# Top.net
KiCad netlist of a schematic drawn in Altium Designer
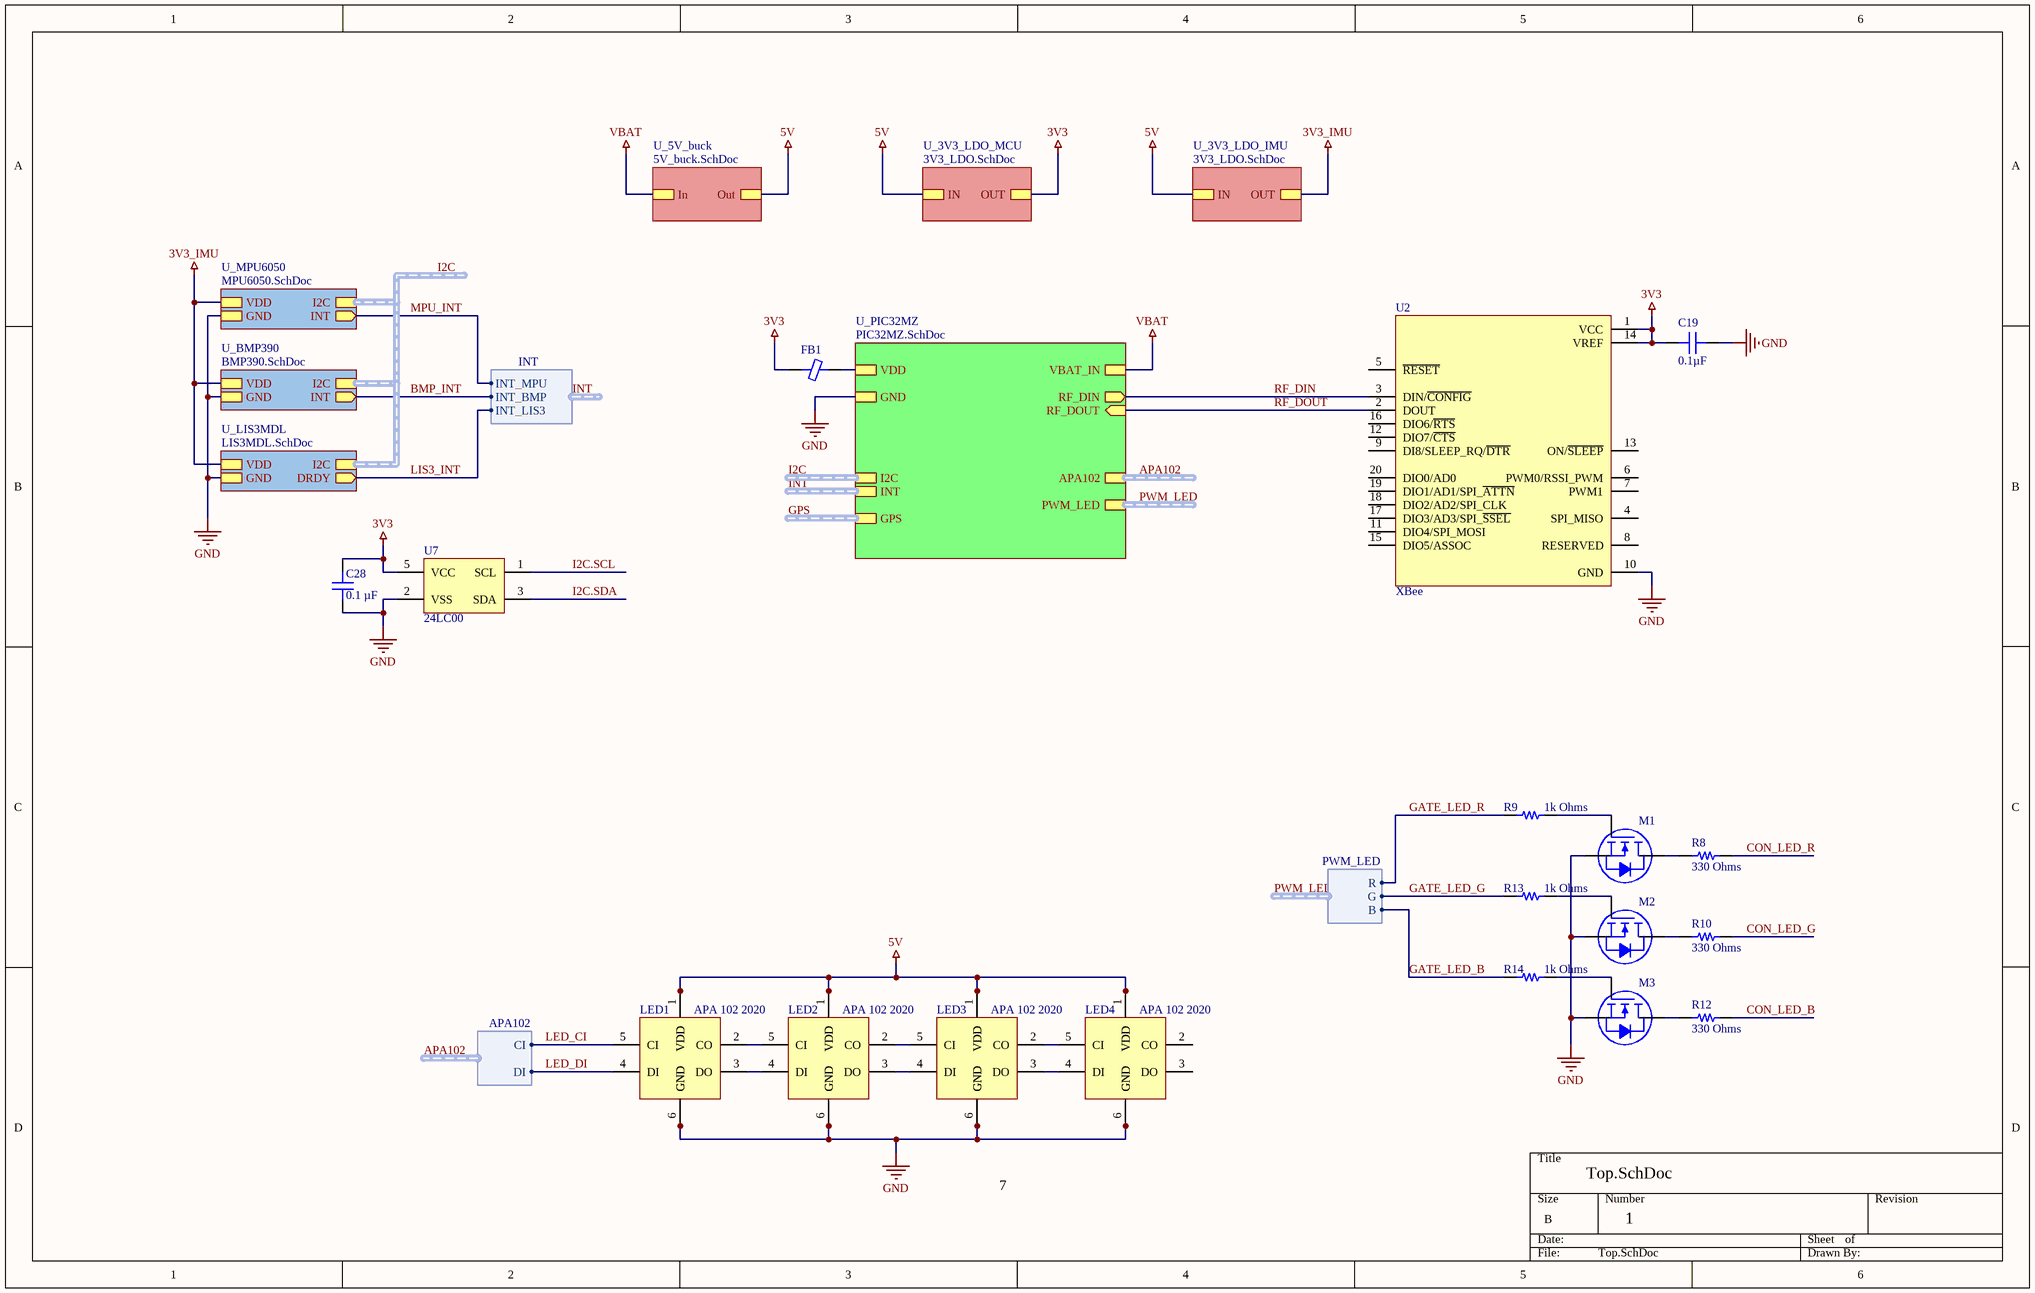
[diagram p0: Top.SchDoc]

(export (version "E")
  (design (tool "Eeschema 10.0.6"))
  (components
    (comp (ref "C19")
      (value "0.1µF")
      (footprint "CAP 0603_1608")
      (description "CAP CER 0.1UF 50V X7R 0603")
      (fields (field (name "PART NUMBER") "LD035C104JAB2A") (field (name "MANUFACTURER") "AVX Corporation"))
      (libsource (lib "Celestial Altium Library - altium_library") (part "Capacitor"))
    )
    (comp (ref "C28")
      (value "0.1 µF")
      (footprint "CAP 0402_1005")
      (description "CAP CER 0.1UF 16V X7R 0402")
      (fields (field (name "PART NUMBER") "C0402C104K4RACAUTO") (field (name "MANUFACTURER") "KEMET"))
      (libsource (lib "Celestial Altium Library - altium_library") (part "Capacitor"))
    )
    (comp (ref "FB1")
      (value "~")
      (footprint "FER 0805_2012")
      (description "FERRITE BEAD 0805 1LN")
      (fields
        (field (name "PART NUMBER") "2508051017Y0")
        (field (name "MANUFACTURER") "Fair-Rite Products Corp.")
      )
      (libsource (lib "Celestial Altium Library - altium_library") (part "Ferrite Chip"))
    )
    (comp (ref "LED1")
      (value "APA 102 2020")
      (footprint "LED_APA-102-2020-256-8")
      (description "8-pin type LED three-color RGB Dimming control")
      (fields (field (name "MP") "APA-102-2020-256-8") (field (name "MF") "iPixel LED Light Co."))
      (libsource (lib "IC") (part "APA-102-2020-256-8"))
    )
    (comp (ref "LED2")
      (value "APA 102 2020")
      (footprint "LED_APA-102-2020-256-8")
      (description "8-pin type LED three-color RGB Dimming control")
      (fields (field (name "MP") "APA-102-2020-256-8") (field (name "MF") "iPixel LED Light Co."))
      (libsource (lib "IC") (part "APA-102-2020-256-8"))
    )
    (comp (ref "LED3")
      (value "APA 102 2020")
      (footprint "LED_APA-102-2020-256-8")
      (description "8-pin type LED three-color RGB Dimming control")
      (fields (field (name "MP") "APA-102-2020-256-8") (field (name "MF") "iPixel LED Light Co."))
      (libsource (lib "IC") (part "APA-102-2020-256-8"))
    )
    (comp (ref "LED4")
      (value "APA 102 2020")
      (footprint "LED_APA-102-2020-256-8")
      (description "8-pin type LED three-color RGB Dimming control")
      (fields (field (name "MP") "APA-102-2020-256-8") (field (name "MF") "iPixel LED Light Co."))
      (libsource (lib "IC") (part "APA-102-2020-256-8"))
    )
    (comp (ref "M1")
      (value "BSS123-7-F")
      (footprint "DIODES SOT-23-3")
      (description "MOSFET N-CH 100V 170MA SOT23-3")
      (fields (field (name "MANUFACTURER") "Diodes Incorporated"))
      (libsource (lib "Celestial Altium Library - altium_library") (part "DIODES INC MOSFET N-CH SOT-23-3"))
    )
    (comp (ref "M2")
      (value "BSS123-7-F")
      (footprint "DIODES SOT-23-3")
      (description "MOSFET N-CH 100V 170MA SOT23-3")
      (fields (field (name "MANUFACTURER") "Diodes Incorporated"))
      (libsource (lib "Celestial Altium Library - altium_library") (part "DIODES INC MOSFET N-CH SOT-23-3"))
    )
    (comp (ref "M3")
      (value "BSS123-7-F")
      (footprint "DIODES SOT-23-3")
      (description "MOSFET N-CH 100V 170MA SOT23-3")
      (fields (field (name "MANUFACTURER") "Diodes Incorporated"))
      (libsource (lib "Celestial Altium Library - altium_library") (part "DIODES INC MOSFET N-CH SOT-23-3"))
    )
    (comp (ref "R8")
      (value "330 Ohms")
      (footprint "RES 0603_1608")
      (description "RES 10K OHM 0.1% 1/16W 0603")
      (fields
        (field (name "PART NUMBER") "RNCS0603BKE10K0")
        (field (name "MANUFACTURER") "Stackpole Electronics Inc")
      )
      (libsource (lib "Celestial Altium Library - altium_library") (part "Resistor"))
    )
    (comp (ref "R9")
      (value "1k Ohms")
      (footprint "RES 0402_1005")
      (description "RES 330 OHM 5% 1/16W 0402")
      (fields (field (name "PART NUMBER") "CRCW0402330RJNEDC") (field (name "MANUFACTURER") "Vishay Dale"))
      (libsource (lib "Celestial Altium Library - altium_library") (part "Resistor"))
    )
    (comp (ref "R10")
      (value "330 Ohms")
      (footprint "RES 0603_1608")
      (description "RES 10K OHM 0.1% 1/16W 0603")
      (fields
        (field (name "PART NUMBER") "RNCS0603BKE10K0")
        (field (name "MANUFACTURER") "Stackpole Electronics Inc")
      )
      (libsource (lib "Celestial Altium Library - altium_library") (part "Resistor"))
    )
    (comp (ref "R12")
      (value "330 Ohms")
      (footprint "RES 0603_1608")
      (description "RES 10K OHM 0.1% 1/16W 0603")
      (fields
        (field (name "PART NUMBER") "RNCS0603BKE10K0")
        (field (name "MANUFACTURER") "Stackpole Electronics Inc")
      )
      (libsource (lib "Celestial Altium Library - altium_library") (part "Resistor"))
    )
    (comp (ref "R13")
      (value "1k Ohms")
      (footprint "RES 0402_1005")
      (description "RES 330 OHM 5% 1/16W 0402")
      (fields (field (name "PART NUMBER") "CRCW0402330RJNEDC") (field (name "MANUFACTURER") "Vishay Dale"))
      (libsource (lib "Celestial Altium Library - altium_library") (part "Resistor"))
    )
    (comp (ref "R14")
      (value "1k Ohms")
      (footprint "RES 0402_1005")
      (description "RES 330 OHM 5% 1/16W 0402")
      (fields (field (name "PART NUMBER") "CRCW0402330RJNEDC") (field (name "MANUFACTURER") "Vishay Dale"))
      (libsource (lib "Celestial Altium Library - altium_library") (part "Resistor"))
    )
    (comp (ref "U2")
      (value "XBee")
      (footprint "XBee")
      (description "802.15.4 Transceiver Module 2.4GHz Antenna Not Included, U.FL Through Hole")
      (libsource (lib "IC") (part "XBee"))
    )
    (comp (ref "U7")
      (value "24LC00")
      (footprint "SOT-23-5")
      (description "EEPROM")
      (libsource (lib "IC") (part "24LC00"))
    )
  )
  (nets
    (net (code "11") (name "/CON_LED_B") (class "Default")
      (node (ref "R12") (pin "2") (pinfunction "2_2") (pintype "passive"))
    )
    (net (code "12") (name "/CON_LED_G") (class "Default")
      (node (ref "R10") (pin "2") (pinfunction "2_2") (pintype "passive"))
    )
    (net (code "13") (name "/CON_LED_R") (class "Default")
      (node (ref "R8") (pin "2") (pinfunction "2_2") (pintype "passive"))
    )
    (net (code "14") (name "/GATE_LED_B") (class "Default")
      (node (ref "R14") (pin "2") (pinfunction "2_2") (pintype "passive"))
    )
    (net (code "15") (name "/GATE_LED_G") (class "Default")
      (node (ref "R13") (pin "2") (pinfunction "2_2") (pintype "passive"))
    )
    (net (code "16") (name "/GATE_LED_R") (class "Default")
      (node (ref "R9") (pin "2") (pinfunction "2_2") (pintype "passive"))
    )
    (net (code "17") (name "/I2C.SCL") (class "Default")
      (node (ref "U7") (pin "1") (pinfunction "SCL_1") (pintype "passive"))
    )
    (net (code "18") (name "/I2C.SDA") (class "Default")
      (node (ref "U7") (pin "3") (pinfunction "SDA_3") (pintype "passive"))
    )
    (net (code "20") (name "/LED_CI") (class "Default")
      (node (ref "LED1") (pin "5") (pinfunction "CI_5") (pintype "passive"))
    )
    (net (code "21") (name "/LED_DI") (class "Default")
      (node (ref "LED1") (pin "4") (pinfunction "DI_4") (pintype "passive"))
    )
    (net (code "25") (name "/RF_DIN") (class "Default")
      (node (ref "U2") (pin "3") (pinfunction "DIN/~{CONFIG}_3") (pintype "passive"))
    )
    (net (code "26") (name "/RF_DOUT") (class "Default")
      (node (ref "U2") (pin "2") (pinfunction "DOUT_2") (pintype "passive"))
    )
    (net (code "27") (name "/VDD") (class "Default")
      (node (ref "FB1") (pin "2") (pinfunction "2_2") (pintype "passive"))
    )
    (net (code "33") (name "3V3") (class "Default")
      (node (ref "C19") (pin "1") (pinfunction "1_1") (pintype "passive"))
      (node (ref "C28") (pin "2") (pinfunction "2_2") (pintype "passive"))
      (node (ref "FB1") (pin "1") (pinfunction "1_1") (pintype "passive"))
      (node (ref "U2") (pin "1") (pinfunction "VCC_1") (pintype "power_in"))
      (node (ref "U2") (pin "14") (pinfunction "VREF_14") (pintype "power_in"))
      (node (ref "U7") (pin "5") (pinfunction "VCC_5") (pintype "passive"))
    )
    (net (code "35") (name "5V") (class "Default")
      (node (ref "LED1") (pin "1") (pinfunction "VDD_1") (pintype "power_in"))
      (node (ref "LED1") (pin "8") (pinfunction "VDD_8") (pintype "power_in"))
      (node (ref "LED2") (pin "1") (pinfunction "VDD_1") (pintype "power_in"))
      (node (ref "LED2") (pin "8") (pinfunction "VDD_8") (pintype "power_in"))
      (node (ref "LED3") (pin "1") (pinfunction "VDD_1") (pintype "power_in"))
      (node (ref "LED3") (pin "8") (pinfunction "VDD_8") (pintype "power_in"))
      (node (ref "LED4") (pin "1") (pinfunction "VDD_1") (pintype "power_in"))
      (node (ref "LED4") (pin "8") (pinfunction "VDD_8") (pintype "power_in"))
    )
    (net (code "36") (name "GND") (class "Default")
      (node (ref "C19") (pin "2") (pinfunction "2_2") (pintype "passive"))
      (node (ref "C28") (pin "1") (pinfunction "1_1") (pintype "passive"))
      (node (ref "LED1") (pin "6") (pinfunction "GND_6") (pintype "power_in"))
      (node (ref "LED1") (pin "7") (pinfunction "GND_7") (pintype "power_in"))
      (node (ref "LED2") (pin "6") (pinfunction "GND_6") (pintype "power_in"))
      (node (ref "LED2") (pin "7") (pinfunction "GND_7") (pintype "power_in"))
      (node (ref "LED3") (pin "6") (pinfunction "GND_6") (pintype "power_in"))
      (node (ref "LED3") (pin "7") (pinfunction "GND_7") (pintype "power_in"))
      (node (ref "LED4") (pin "6") (pinfunction "GND_6") (pintype "power_in"))
      (node (ref "LED4") (pin "7") (pinfunction "GND_7") (pintype "power_in"))
      (node (ref "M1") (pin "2") (pinfunction "S_2") (pintype "passive"))
      (node (ref "M2") (pin "2") (pinfunction "S_2") (pintype "passive"))
      (node (ref "M3") (pin "2") (pinfunction "S_2") (pintype "passive"))
      (node (ref "U2") (pin "10") (pinfunction "GND_10") (pintype "power_in"))
      (node (ref "U7") (pin "2") (pinfunction "VSS_2") (pintype "passive"))
    )
    (net (code "37") (name "Net-(LED1-CO)") (class "Default")
      (node (ref "LED1") (pin "2") (pinfunction "CO_2") (pintype "passive"))
      (node (ref "LED2") (pin "5") (pinfunction "CI_5") (pintype "passive"))
    )
    (net (code "38") (name "Net-(LED1-DO)") (class "Default")
      (node (ref "LED1") (pin "3") (pinfunction "DO_3") (pintype "passive"))
      (node (ref "LED2") (pin "4") (pinfunction "DI_4") (pintype "passive"))
    )
    (net (code "39") (name "Net-(LED2-CO)") (class "Default")
      (node (ref "LED2") (pin "2") (pinfunction "CO_2") (pintype "passive"))
      (node (ref "LED3") (pin "5") (pinfunction "CI_5") (pintype "passive"))
    )
    (net (code "40") (name "Net-(LED2-DO)") (class "Default")
      (node (ref "LED2") (pin "3") (pinfunction "DO_3") (pintype "passive"))
      (node (ref "LED3") (pin "4") (pinfunction "DI_4") (pintype "passive"))
    )
    (net (code "41") (name "Net-(LED3-CO)") (class "Default")
      (node (ref "LED3") (pin "2") (pinfunction "CO_2") (pintype "passive"))
      (node (ref "LED4") (pin "5") (pinfunction "CI_5") (pintype "passive"))
    )
    (net (code "42") (name "Net-(LED3-DO)") (class "Default")
      (node (ref "LED3") (pin "3") (pinfunction "DO_3") (pintype "passive"))
      (node (ref "LED4") (pin "4") (pinfunction "DI_4") (pintype "passive"))
    )
    (net (code "43") (name "Net-(M1-D)") (class "Default")
      (node (ref "M1") (pin "3") (pinfunction "D_3") (pintype "passive"))
      (node (ref "R8") (pin "1") (pinfunction "1_1") (pintype "passive"))
    )
    (net (code "44") (name "Net-(M1-G)") (class "Default")
      (node (ref "M1") (pin "1") (pinfunction "G_1") (pintype "passive"))
      (node (ref "R9") (pin "1") (pinfunction "1_1") (pintype "passive"))
    )
    (net (code "45") (name "Net-(M2-D)") (class "Default")
      (node (ref "M2") (pin "3") (pinfunction "D_3") (pintype "passive"))
      (node (ref "R10") (pin "1") (pinfunction "1_1") (pintype "passive"))
    )
    (net (code "46") (name "Net-(M2-G)") (class "Default")
      (node (ref "M2") (pin "1") (pinfunction "G_1") (pintype "passive"))
      (node (ref "R13") (pin "1") (pinfunction "1_1") (pintype "passive"))
    )
    (net (code "47") (name "Net-(M3-D)") (class "Default")
      (node (ref "M3") (pin "3") (pinfunction "D_3") (pintype "passive"))
      (node (ref "R12") (pin "1") (pinfunction "1_1") (pintype "passive"))
    )
    (net (code "48") (name "Net-(M3-G)") (class "Default")
      (node (ref "M3") (pin "1") (pinfunction "G_1") (pintype "passive"))
      (node (ref "R14") (pin "1") (pinfunction "1_1") (pintype "passive"))
    )
    (net (code "50") (name "unconnected-(LED4-CO-Pad2)") (class "Default")
      (node (ref "LED4") (pin "2") (pinfunction "CO_2") (pintype "passive"))
    )
    (net (code "51") (name "unconnected-(LED4-DO-Pad3)") (class "Default")
      (node (ref "LED4") (pin "3") (pinfunction "DO_3") (pintype "passive"))
    )
    (net (code "52") (name "unconnected-(U2-DI8{slash}SLEEP_RQ{slash}~{DTR}-Pad9)") (class "Default")
      (node (ref "U2") (pin "9") (pinfunction "DI8/SLEEP_RQ/~{DTR}_9") (pintype "passive"))
    )
    (net (code "53") (name "unconnected-(U2-DIO0{slash}AD0-Pad20)") (class "Default")
      (node (ref "U2") (pin "20") (pinfunction "DIO0/AD0_20") (pintype "passive"))
    )
    (net (code "54") (name "unconnected-(U2-DIO1{slash}AD1{slash}SPI_~{ATTN}-Pad19)") (class "Default")
      (node (ref "U2") (pin "19") (pinfunction "DIO1/AD1/SPI_~{ATTN}_19") (pintype "passive"))
    )
    (net (code "55") (name "unconnected-(U2-DIO2{slash}AD2{slash}SPI_CLK-Pad18)") (class "Default")
      (node (ref "U2") (pin "18") (pinfunction "DIO2/AD2/SPI_CLK_18") (pintype "passive"))
    )
    (net (code "56") (name "unconnected-(U2-DIO3{slash}AD3{slash}SPI_~{SSEL}-Pad17)") (class "Default")
      (node (ref "U2") (pin "17") (pinfunction "DIO3/AD3/SPI_~{SSEL}_17") (pintype "passive"))
    )
    (net (code "57") (name "unconnected-(U2-DIO4{slash}SPI_MOSI-Pad11)") (class "Default")
      (node (ref "U2") (pin "11") (pinfunction "DIO4/SPI_MOSI_11") (pintype "passive"))
    )
    (net (code "58") (name "unconnected-(U2-DIO5{slash}ASSOC-Pad15)") (class "Default")
      (node (ref "U2") (pin "15") (pinfunction "DIO5/ASSOC_15") (pintype "passive"))
    )
    (net (code "59") (name "unconnected-(U2-DIO6{slash}~{RTS}-Pad16)") (class "Default")
      (node (ref "U2") (pin "16") (pinfunction "DIO6/~{RTS}_16") (pintype "passive"))
    )
    (net (code "60") (name "unconnected-(U2-DIO7{slash}~{CTS}-Pad12)") (class "Default")
      (node (ref "U2") (pin "12") (pinfunction "DIO7/~{CTS}_12") (pintype "passive"))
    )
    (net (code "61") (name "unconnected-(U2-ON{slash}~{SLEEP}-Pad13)") (class "Default")
      (node (ref "U2") (pin "13") (pinfunction "ON/~{SLEEP}_13") (pintype "passive"))
    )
    (net (code "62") (name "unconnected-(U2-PWM0{slash}RSSI_PWM-Pad6)") (class "Default")
      (node (ref "U2") (pin "6") (pinfunction "PWM0/RSSI_PWM_6") (pintype "passive"))
    )
    (net (code "63") (name "unconnected-(U2-PWM1-Pad7)") (class "Default")
      (node (ref "U2") (pin "7") (pinfunction "PWM1_7") (pintype "passive"))
    )
    (net (code "64") (name "unconnected-(U2-RESERVED-Pad8)") (class "Default")
      (node (ref "U2") (pin "8") (pinfunction "RESERVED_8") (pintype "passive"))
    )
    (net (code "65") (name "unconnected-(U2-SPI_MISO-Pad4)") (class "Default")
      (node (ref "U2") (pin "4") (pinfunction "SPI_MISO_4") (pintype "passive"))
    )
    (net (code "66") (name "unconnected-(U2-~{RESET}-Pad5)") (class "Default")
      (node (ref "U2") (pin "5") (pinfunction "~{RESET}_5") (pintype "passive"))
    )
  )
)
